# BACK-LIGHT.net
KiCad netlist of a schematic drawn in Altium Designer
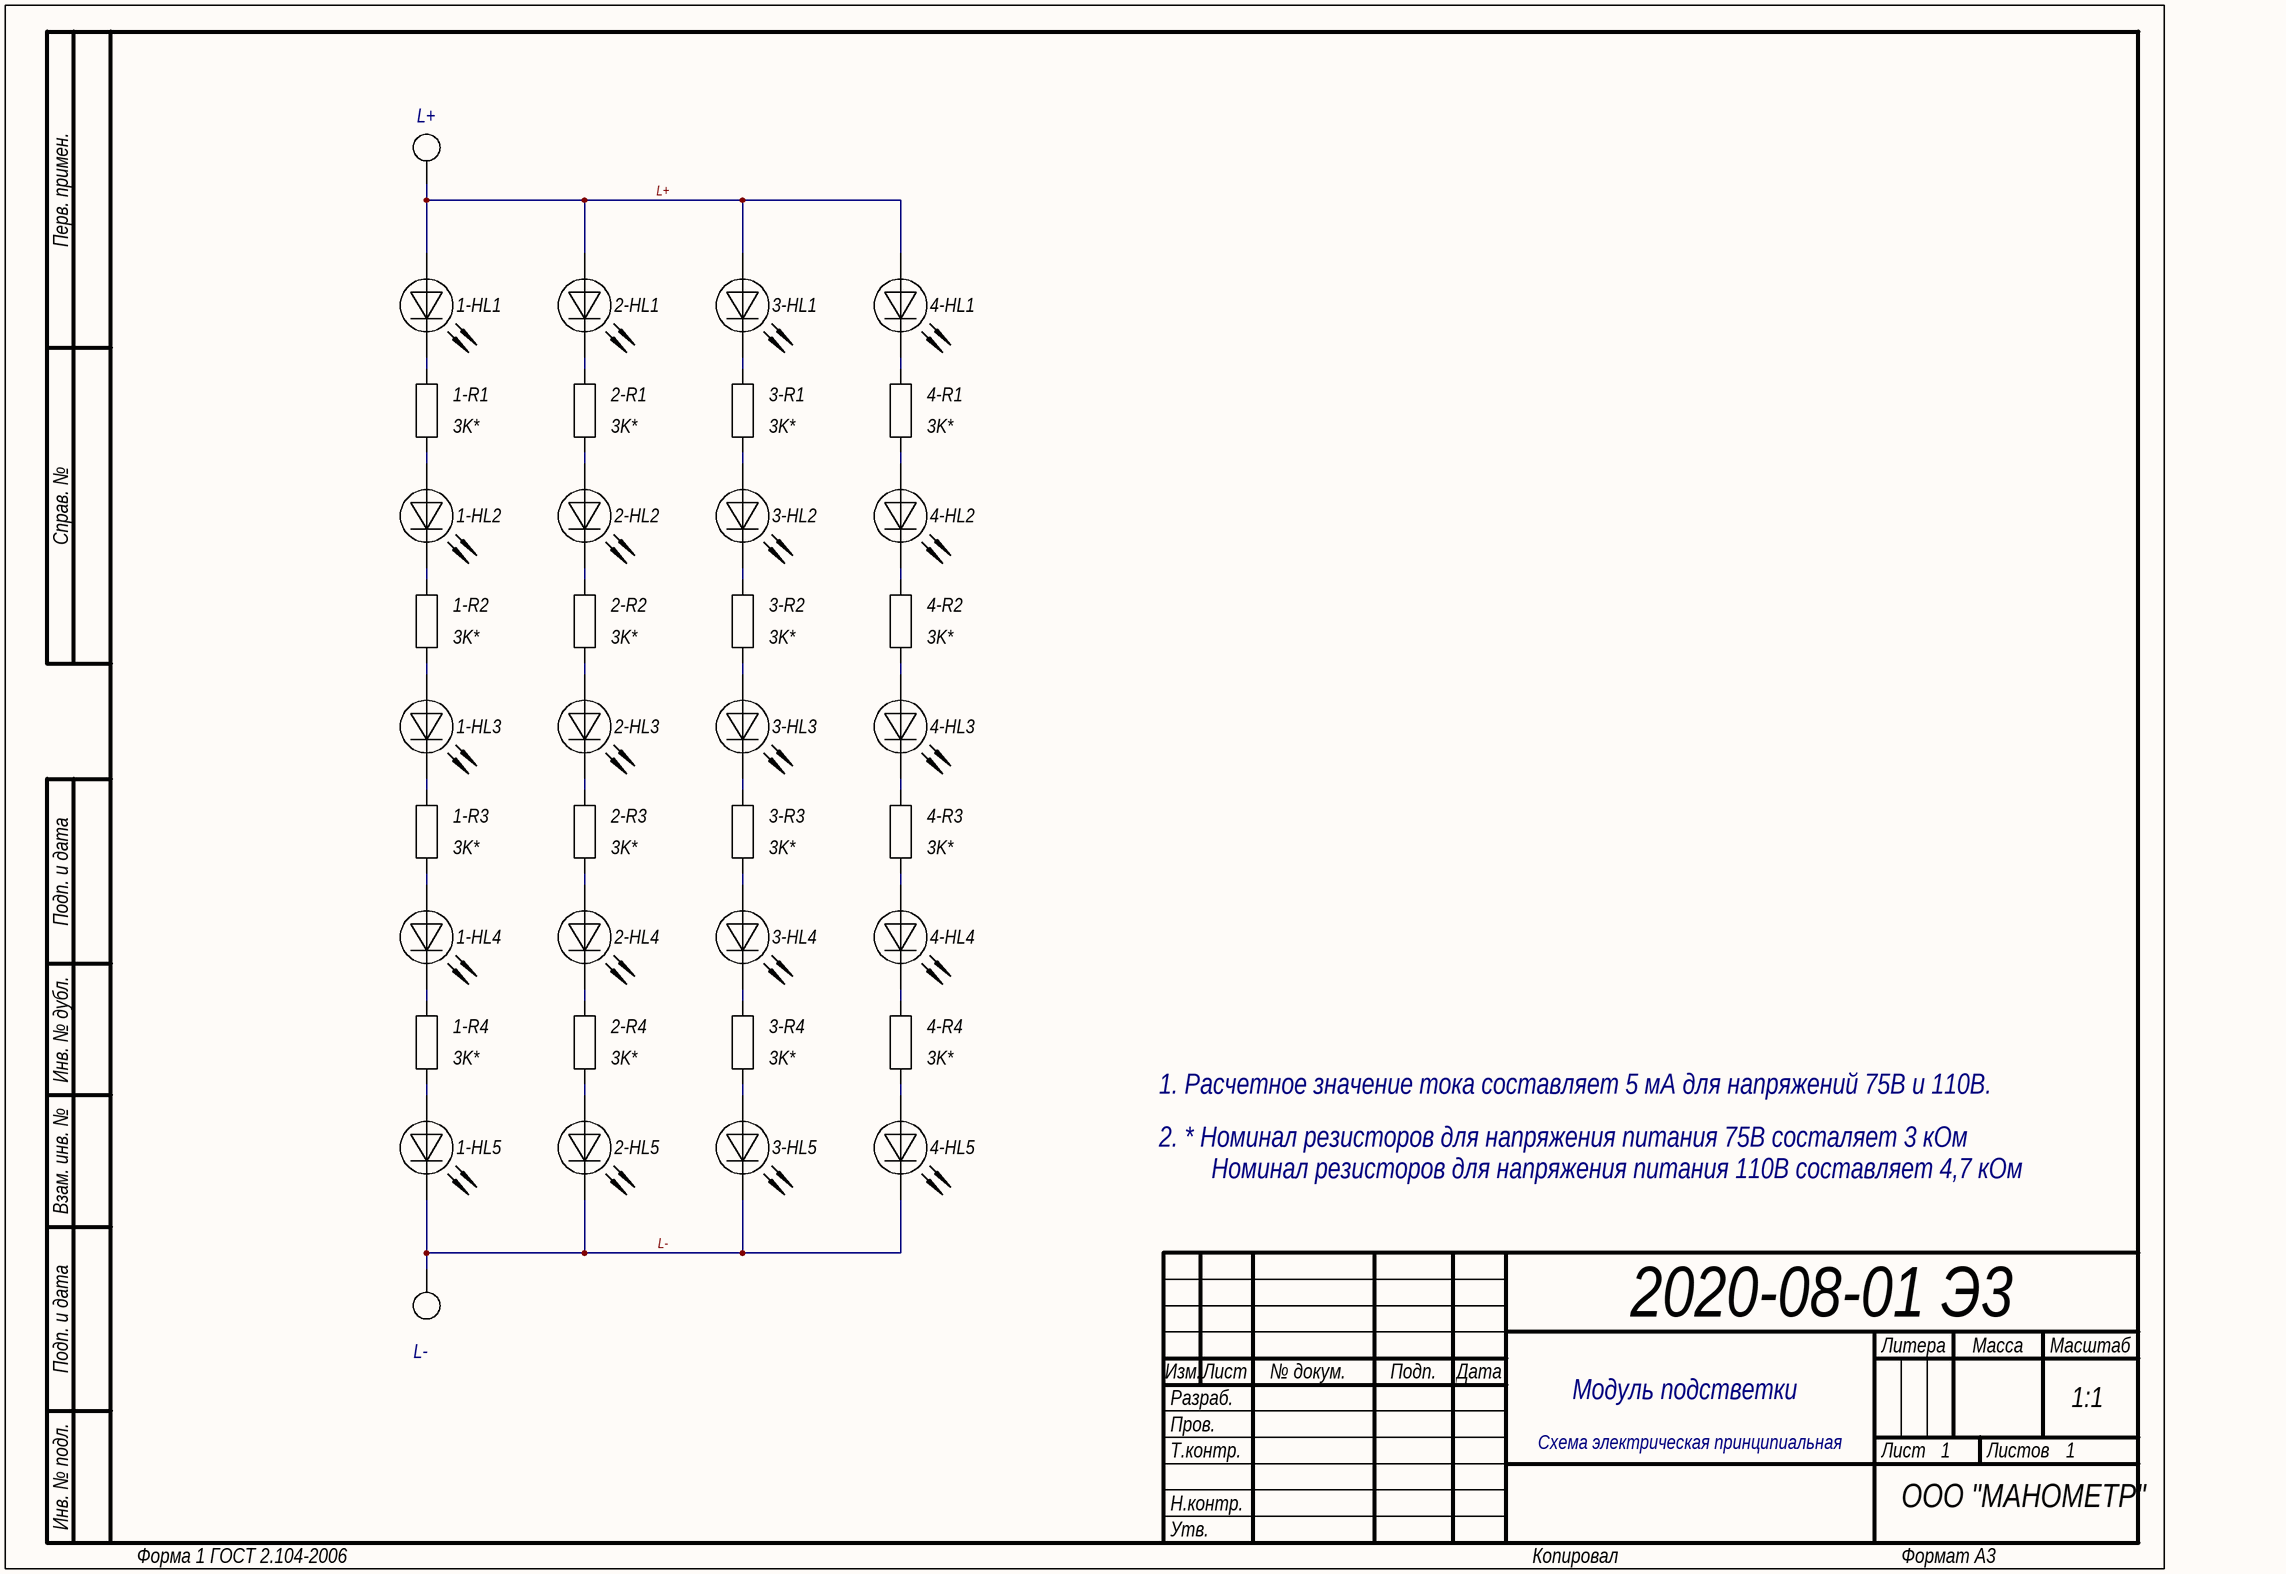
[diagram p0: BACK-LIGHT.SchDoc]

(export (version "E")
  (design (tool "Eeschema 10.0.6"))
  (components
    (comp (ref "1-HL1")
      (value "FYLS-1206UWC")
      (footprint "LED 1206")
      (description "Светодиод")
      (fields (field (name "TOLERANCE") "3K*"))
      (libsource (lib "MAXX") (part "LED"))
    )
    (comp (ref "1-HL2")
      (value "FYLS-1206UWC")
      (footprint "LED 1206")
      (description "Светодиод")
      (fields (field (name "TOLERANCE") "3K*"))
      (libsource (lib "MAXX") (part "LED"))
    )
    (comp (ref "1-HL3")
      (value "FYLS-1206UWC")
      (footprint "LED 1206")
      (description "Светодиод")
      (fields (field (name "TOLERANCE") "3K*"))
      (libsource (lib "MAXX") (part "LED"))
    )
    (comp (ref "1-HL4")
      (value "FYLS-1206UWC")
      (footprint "LED 1206")
      (description "Светодиод")
      (fields (field (name "TOLERANCE") "3K*"))
      (libsource (lib "MAXX") (part "LED"))
    )
    (comp (ref "1-HL5")
      (value "FYLS-1206UWC")
      (footprint "LED 1206")
      (description "Светодиод")
      (fields (field (name "TOLERANCE") "3K*"))
      (libsource (lib "MAXX") (part "LED"))
    )
    (comp (ref "1-R1")
      (value "3K*")
      (footprint "RC1206")
      (description "Постоянный углеродистый резистор")
      (libsource (lib "MAXX") (part "RES"))
    )
    (comp (ref "1-R2")
      (value "3K*")
      (footprint "RC1206")
      (description "Постоянный углеродистый резистор")
      (libsource (lib "MAXX") (part "RES"))
    )
    (comp (ref "1-R3")
      (value "3K*")
      (footprint "RC1206")
      (description "Постоянный углеродистый резистор")
      (libsource (lib "MAXX") (part "RES"))
    )
    (comp (ref "1-R4")
      (value "3K*")
      (footprint "RC1206")
      (description "Постоянный углеродистый резистор")
      (libsource (lib "MAXX") (part "RES"))
    )
    (comp (ref "2-HL1")
      (value "FYLS-1206UWC")
      (footprint "LED 1206")
      (description "Светодиод")
      (fields (field (name "TOLERANCE") "3K*"))
      (libsource (lib "MAXX") (part "LED"))
    )
    (comp (ref "2-HL2")
      (value "FYLS-1206UWC")
      (footprint "LED 1206")
      (description "Светодиод")
      (fields (field (name "TOLERANCE") "3K*"))
      (libsource (lib "MAXX") (part "LED"))
    )
    (comp (ref "2-HL3")
      (value "FYLS-1206UWC")
      (footprint "LED 1206")
      (description "Светодиод")
      (fields (field (name "TOLERANCE") "3K*"))
      (libsource (lib "MAXX") (part "LED"))
    )
    (comp (ref "2-HL4")
      (value "FYLS-1206UWC")
      (footprint "LED 1206")
      (description "Светодиод")
      (fields (field (name "TOLERANCE") "3K*"))
      (libsource (lib "MAXX") (part "LED"))
    )
    (comp (ref "2-HL5")
      (value "FYLS-1206UWC")
      (footprint "LED 1206")
      (description "Светодиод")
      (fields (field (name "TOLERANCE") "3K*"))
      (libsource (lib "MAXX") (part "LED"))
    )
    (comp (ref "2-R1")
      (value "3K*")
      (footprint "RC1206")
      (description "Постоянный углеродистый резистор")
      (libsource (lib "MAXX") (part "RES"))
    )
    (comp (ref "2-R2")
      (value "3K*")
      (footprint "RC1206")
      (description "Постоянный углеродистый резистор")
      (libsource (lib "MAXX") (part "RES"))
    )
    (comp (ref "2-R3")
      (value "3K*")
      (footprint "RC1206")
      (description "Постоянный углеродистый резистор")
      (libsource (lib "MAXX") (part "RES"))
    )
    (comp (ref "2-R4")
      (value "3K*")
      (footprint "RC1206")
      (description "Постоянный углеродистый резистор")
      (libsource (lib "MAXX") (part "RES"))
    )
    (comp (ref "3-HL1")
      (value "FYLS-1206UWC")
      (footprint "LED 1206")
      (description "Светодиод")
      (fields (field (name "TOLERANCE") "3K*"))
      (libsource (lib "MAXX") (part "LED"))
    )
    (comp (ref "3-HL2")
      (value "FYLS-1206UWC")
      (footprint "LED 1206")
      (description "Светодиод")
      (fields (field (name "TOLERANCE") "3K*"))
      (libsource (lib "MAXX") (part "LED"))
    )
    (comp (ref "3-HL3")
      (value "FYLS-1206UWC")
      (footprint "LED 1206")
      (description "Светодиод")
      (fields (field (name "TOLERANCE") "3K*"))
      (libsource (lib "MAXX") (part "LED"))
    )
    (comp (ref "3-HL4")
      (value "FYLS-1206UWC")
      (footprint "LED 1206")
      (description "Светодиод")
      (fields (field (name "TOLERANCE") "3K*"))
      (libsource (lib "MAXX") (part "LED"))
    )
    (comp (ref "3-HL5")
      (value "FYLS-1206UWC")
      (footprint "LED 1206")
      (description "Светодиод")
      (fields (field (name "TOLERANCE") "3K*"))
      (libsource (lib "MAXX") (part "LED"))
    )
    (comp (ref "3-R1")
      (value "3K*")
      (footprint "RC1206")
      (description "Постоянный углеродистый резистор")
      (libsource (lib "MAXX") (part "RES"))
    )
    (comp (ref "3-R2")
      (value "3K*")
      (footprint "RC1206")
      (description "Постоянный углеродистый резистор")
      (libsource (lib "MAXX") (part "RES"))
    )
    (comp (ref "3-R3")
      (value "3K*")
      (footprint "RC1206")
      (description "Постоянный углеродистый резистор")
      (libsource (lib "MAXX") (part "RES"))
    )
    (comp (ref "3-R4")
      (value "3K*")
      (footprint "RC1206")
      (description "Постоянный углеродистый резистор")
      (libsource (lib "MAXX") (part "RES"))
    )
    (comp (ref "4-HL1")
      (value "FYLS-1206UWC")
      (footprint "LED 1206")
      (description "Светодиод")
      (fields (field (name "TOLERANCE") "3K*"))
      (libsource (lib "MAXX") (part "LED"))
    )
    (comp (ref "4-HL2")
      (value "FYLS-1206UWC")
      (footprint "LED 1206")
      (description "Светодиод")
      (fields (field (name "TOLERANCE") "3K*"))
      (libsource (lib "MAXX") (part "LED"))
    )
    (comp (ref "4-HL3")
      (value "FYLS-1206UWC")
      (footprint "LED 1206")
      (description "Светодиод")
      (fields (field (name "TOLERANCE") "3K*"))
      (libsource (lib "MAXX") (part "LED"))
    )
    (comp (ref "4-HL4")
      (value "FYLS-1206UWC")
      (footprint "LED 1206")
      (description "Светодиод")
      (fields (field (name "TOLERANCE") "3K*"))
      (libsource (lib "MAXX") (part "LED"))
    )
    (comp (ref "4-HL5")
      (value "FYLS-1206UWC")
      (footprint "LED 1206")
      (description "Светодиод")
      (fields (field (name "TOLERANCE") "3K*"))
      (libsource (lib "MAXX") (part "LED"))
    )
    (comp (ref "4-R1")
      (value "3K*")
      (footprint "RC1206")
      (description "Постоянный углеродистый резистор")
      (libsource (lib "MAXX") (part "RES"))
    )
    (comp (ref "4-R2")
      (value "3K*")
      (footprint "RC1206")
      (description "Постоянный углеродистый резистор")
      (libsource (lib "MAXX") (part "RES"))
    )
    (comp (ref "4-R3")
      (value "3K*")
      (footprint "RC1206")
      (description "Постоянный углеродистый резистор")
      (libsource (lib "MAXX") (part "RES"))
    )
    (comp (ref "4-R4")
      (value "3K*")
      (footprint "RC1206")
      (description "Постоянный углеродистый резистор")
      (libsource (lib "MAXX") (part "RES"))
    )
    (comp (ref "L+") (value "~") (footprint "PIN") (libsource (lib "MAXX") (part "PIN")))
    (comp (ref "L-") (value "~") (footprint "PIN") (libsource (lib "MAXX") (part "PIN")))
  )
  (nets
    (net (code "1") (name "/L+") (class "Default")
      (node (ref "1-HL1") (pin "1") (pinfunction "A_1") (pintype "passive"))
      (node (ref "2-HL1") (pin "1") (pinfunction "A_1") (pintype "passive"))
      (node (ref "3-HL1") (pin "1") (pinfunction "A_1") (pintype "passive"))
      (node (ref "4-HL1") (pin "1") (pinfunction "A_1") (pintype "passive"))
      (node (ref "L+") (pin "PIN") (pinfunction "PIN_PIN") (pintype "passive"))
    )
    (net (code "2") (name "/L-") (class "Default")
      (node (ref "1-HL5") (pin "2") (pinfunction "K_2") (pintype "passive"))
      (node (ref "2-HL5") (pin "2") (pinfunction "K_2") (pintype "passive"))
      (node (ref "3-HL5") (pin "2") (pinfunction "K_2") (pintype "passive"))
      (node (ref "4-HL5") (pin "2") (pinfunction "K_2") (pintype "passive"))
      (node (ref "L-") (pin "PIN") (pinfunction "PIN_PIN") (pintype "passive"))
    )
    (net (code "3") (name "Net-(1-HL1-K)") (class "Default")
      (node (ref "1-HL1") (pin "2") (pinfunction "K_2") (pintype "passive"))
      (node (ref "1-R1") (pin "1") (pinfunction "1_1") (pintype "passive"))
    )
    (net (code "4") (name "Net-(1-HL2-A)") (class "Default")
      (node (ref "1-HL2") (pin "1") (pinfunction "A_1") (pintype "passive"))
      (node (ref "1-R1") (pin "2") (pinfunction "2_2") (pintype "passive"))
    )
    (net (code "5") (name "Net-(1-HL2-K)") (class "Default")
      (node (ref "1-HL2") (pin "2") (pinfunction "K_2") (pintype "passive"))
      (node (ref "1-R2") (pin "1") (pinfunction "1_1") (pintype "passive"))
    )
    (net (code "6") (name "Net-(1-HL3-A)") (class "Default")
      (node (ref "1-HL3") (pin "1") (pinfunction "A_1") (pintype "passive"))
      (node (ref "1-R2") (pin "2") (pinfunction "2_2") (pintype "passive"))
    )
    (net (code "7") (name "Net-(1-HL3-K)") (class "Default")
      (node (ref "1-HL3") (pin "2") (pinfunction "K_2") (pintype "passive"))
      (node (ref "1-R3") (pin "1") (pinfunction "1_1") (pintype "passive"))
    )
    (net (code "8") (name "Net-(1-HL4-A)") (class "Default")
      (node (ref "1-HL4") (pin "1") (pinfunction "A_1") (pintype "passive"))
      (node (ref "1-R3") (pin "2") (pinfunction "2_2") (pintype "passive"))
    )
    (net (code "9") (name "Net-(1-HL4-K)") (class "Default")
      (node (ref "1-HL4") (pin "2") (pinfunction "K_2") (pintype "passive"))
      (node (ref "1-R4") (pin "1") (pinfunction "1_1") (pintype "passive"))
    )
    (net (code "10") (name "Net-(1-HL5-A)") (class "Default")
      (node (ref "1-HL5") (pin "1") (pinfunction "A_1") (pintype "passive"))
      (node (ref "1-R4") (pin "2") (pinfunction "2_2") (pintype "passive"))
    )
    (net (code "11") (name "Net-(2-HL1-K)") (class "Default")
      (node (ref "2-HL1") (pin "2") (pinfunction "K_2") (pintype "passive"))
      (node (ref "2-R1") (pin "1") (pinfunction "1_1") (pintype "passive"))
    )
    (net (code "12") (name "Net-(2-HL2-A)") (class "Default")
      (node (ref "2-HL2") (pin "1") (pinfunction "A_1") (pintype "passive"))
      (node (ref "2-R1") (pin "2") (pinfunction "2_2") (pintype "passive"))
    )
    (net (code "13") (name "Net-(2-HL2-K)") (class "Default")
      (node (ref "2-HL2") (pin "2") (pinfunction "K_2") (pintype "passive"))
      (node (ref "2-R2") (pin "1") (pinfunction "1_1") (pintype "passive"))
    )
    (net (code "14") (name "Net-(2-HL3-A)") (class "Default")
      (node (ref "2-HL3") (pin "1") (pinfunction "A_1") (pintype "passive"))
      (node (ref "2-R2") (pin "2") (pinfunction "2_2") (pintype "passive"))
    )
    (net (code "15") (name "Net-(2-HL3-K)") (class "Default")
      (node (ref "2-HL3") (pin "2") (pinfunction "K_2") (pintype "passive"))
      (node (ref "2-R3") (pin "1") (pinfunction "1_1") (pintype "passive"))
    )
    (net (code "16") (name "Net-(2-HL4-A)") (class "Default")
      (node (ref "2-HL4") (pin "1") (pinfunction "A_1") (pintype "passive"))
      (node (ref "2-R3") (pin "2") (pinfunction "2_2") (pintype "passive"))
    )
    (net (code "17") (name "Net-(2-HL4-K)") (class "Default")
      (node (ref "2-HL4") (pin "2") (pinfunction "K_2") (pintype "passive"))
      (node (ref "2-R4") (pin "1") (pinfunction "1_1") (pintype "passive"))
    )
    (net (code "18") (name "Net-(2-HL5-A)") (class "Default")
      (node (ref "2-HL5") (pin "1") (pinfunction "A_1") (pintype "passive"))
      (node (ref "2-R4") (pin "2") (pinfunction "2_2") (pintype "passive"))
    )
    (net (code "19") (name "Net-(3-HL1-K)") (class "Default")
      (node (ref "3-HL1") (pin "2") (pinfunction "K_2") (pintype "passive"))
      (node (ref "3-R1") (pin "1") (pinfunction "1_1") (pintype "passive"))
    )
    (net (code "20") (name "Net-(3-HL2-A)") (class "Default")
      (node (ref "3-HL2") (pin "1") (pinfunction "A_1") (pintype "passive"))
      (node (ref "3-R1") (pin "2") (pinfunction "2_2") (pintype "passive"))
    )
    (net (code "21") (name "Net-(3-HL2-K)") (class "Default")
      (node (ref "3-HL2") (pin "2") (pinfunction "K_2") (pintype "passive"))
      (node (ref "3-R2") (pin "1") (pinfunction "1_1") (pintype "passive"))
    )
    (net (code "22") (name "Net-(3-HL3-A)") (class "Default")
      (node (ref "3-HL3") (pin "1") (pinfunction "A_1") (pintype "passive"))
      (node (ref "3-R2") (pin "2") (pinfunction "2_2") (pintype "passive"))
    )
    (net (code "23") (name "Net-(3-HL3-K)") (class "Default")
      (node (ref "3-HL3") (pin "2") (pinfunction "K_2") (pintype "passive"))
      (node (ref "3-R3") (pin "1") (pinfunction "1_1") (pintype "passive"))
    )
    (net (code "24") (name "Net-(3-HL4-A)") (class "Default")
      (node (ref "3-HL4") (pin "1") (pinfunction "A_1") (pintype "passive"))
      (node (ref "3-R3") (pin "2") (pinfunction "2_2") (pintype "passive"))
    )
    (net (code "25") (name "Net-(3-HL4-K)") (class "Default")
      (node (ref "3-HL4") (pin "2") (pinfunction "K_2") (pintype "passive"))
      (node (ref "3-R4") (pin "1") (pinfunction "1_1") (pintype "passive"))
    )
    (net (code "26") (name "Net-(3-HL5-A)") (class "Default")
      (node (ref "3-HL5") (pin "1") (pinfunction "A_1") (pintype "passive"))
      (node (ref "3-R4") (pin "2") (pinfunction "2_2") (pintype "passive"))
    )
    (net (code "27") (name "Net-(4-HL1-K)") (class "Default")
      (node (ref "4-HL1") (pin "2") (pinfunction "K_2") (pintype "passive"))
      (node (ref "4-R1") (pin "1") (pinfunction "1_1") (pintype "passive"))
    )
    (net (code "28") (name "Net-(4-HL2-A)") (class "Default")
      (node (ref "4-HL2") (pin "1") (pinfunction "A_1") (pintype "passive"))
      (node (ref "4-R1") (pin "2") (pinfunction "2_2") (pintype "passive"))
    )
    (net (code "29") (name "Net-(4-HL2-K)") (class "Default")
      (node (ref "4-HL2") (pin "2") (pinfunction "K_2") (pintype "passive"))
      (node (ref "4-R2") (pin "1") (pinfunction "1_1") (pintype "passive"))
    )
    (net (code "30") (name "Net-(4-HL3-A)") (class "Default")
      (node (ref "4-HL3") (pin "1") (pinfunction "A_1") (pintype "passive"))
      (node (ref "4-R2") (pin "2") (pinfunction "2_2") (pintype "passive"))
    )
    (net (code "31") (name "Net-(4-HL3-K)") (class "Default")
      (node (ref "4-HL3") (pin "2") (pinfunction "K_2") (pintype "passive"))
      (node (ref "4-R3") (pin "1") (pinfunction "1_1") (pintype "passive"))
    )
    (net (code "32") (name "Net-(4-HL4-A)") (class "Default")
      (node (ref "4-HL4") (pin "1") (pinfunction "A_1") (pintype "passive"))
      (node (ref "4-R3") (pin "2") (pinfunction "2_2") (pintype "passive"))
    )
    (net (code "33") (name "Net-(4-HL4-K)") (class "Default")
      (node (ref "4-HL4") (pin "2") (pinfunction "K_2") (pintype "passive"))
      (node (ref "4-R4") (pin "1") (pinfunction "1_1") (pintype "passive"))
    )
    (net (code "34") (name "Net-(4-HL5-A)") (class "Default")
      (node (ref "4-HL5") (pin "1") (pinfunction "A_1") (pintype "passive"))
      (node (ref "4-R4") (pin "2") (pinfunction "2_2") (pintype "passive"))
    )
  )
)
